# 04-UserIO.net
KiCad netlist of a schematic drawn in Altium Designer
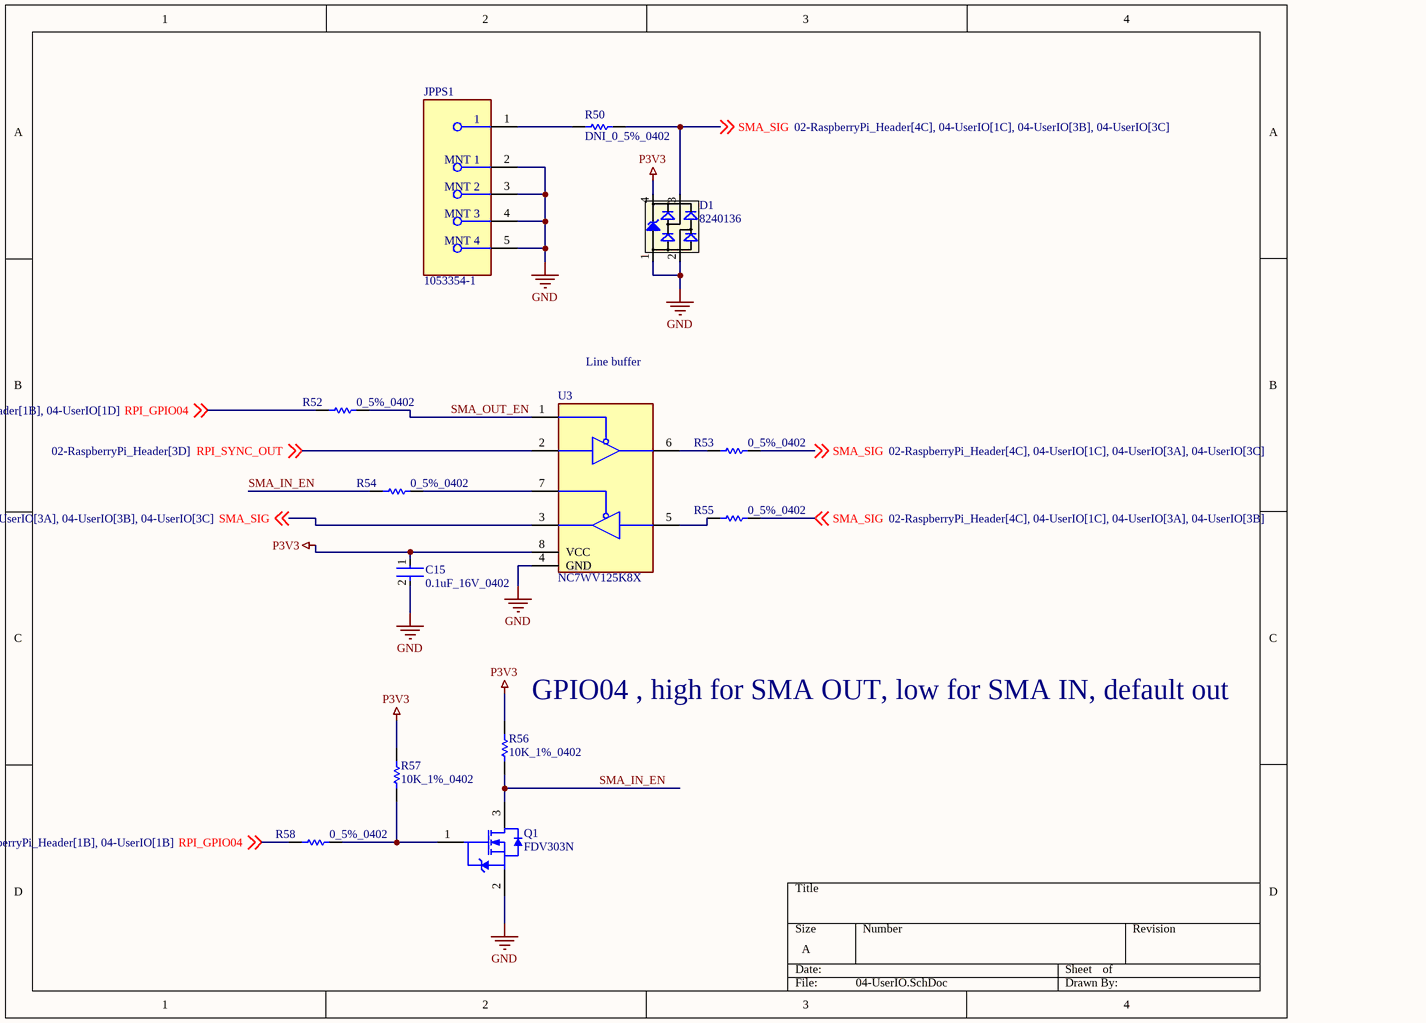
[diagram p0: 04-UserIO.SchDoc]

(export (version "E")
  (design (tool "Eeschema 10.0.6"))
  (components
    (comp (ref "C15")
      (value "0.1uF_16V_0402")
      (footprint "FP-GRM15-MFG")
      (description "CAP CER 0.1UF 16V X7R 0402")
      (fields (field (name "MANUFACTURER PART NUMBER") "GRM155R71C104KA88D") (field (name "TOLERANCE") "10%"))
      (libsource (lib "Altium Content Vault") (part "236180d848d6139a670b325ea6854c9"))
    )
    (comp (ref "D1")
      (value "8240136")
      (footprint "SOT143-4L")
      (description "TVS Diode WE-TVS-HS, VRWM=3.3V")
      (fields (field (name "MANUFACTURER") "Wuerth Elektronik"))
      (libsource (lib "Altium Content Vault") (part "WE-TVS-HS-4"))
    )
    (comp (ref "JPPS1")
      (value "1053354-1")
      (footprint "FP-1053354-1-MFG")
      (description "CONN SMA JACK STR 50 OHM PCB")
      (libsource (lib "Altium Content Vault") (part "c65b8a639cdaef1819ea20b5466f8fa"))
    )
    (comp (ref "Q1")
      (value "FDV303N")
      (footprint "FAIR-FDV303N-3_V")
      (fields (field (name "MANUFACTURER") "Fairchild"))
      (libsource (lib "Altium Content Vault") (part "NEMOS-GSD-3_D"))
    )
    (comp (ref "R50")
      (value "DNI_0_5%_0402")
      (footprint "RESC1005X40X25NL05T10")
      (fields (field (name "MANUFACTURER") "Yageo / Phycomp") (field (name "PART NUMBER") "RC0402JR-070RL"))
      (libsource (lib "Altium Content Vault") (part "RES"))
    )
    (comp (ref "R52")
      (value "0_5%_0402")
      (footprint "RESC1005X40X25NL05T10")
      (fields (field (name "MANUFACTURER") "Yageo / Phycomp") (field (name "PART NUMBER") "RC0402JR-070RL"))
      (libsource (lib "Altium Content Vault") (part "RES"))
    )
    (comp (ref "R53")
      (value "0_5%_0402")
      (footprint "RESC1005X40X25NL05T10")
      (fields (field (name "MANUFACTURER") "Yageo / Phycomp") (field (name "PART NUMBER") "RC0402JR-070RL"))
      (libsource (lib "Altium Content Vault") (part "RES"))
    )
    (comp (ref "R54")
      (value "0_5%_0402")
      (footprint "RESC1005X40X25NL05T10")
      (fields (field (name "MANUFACTURER") "Yageo / Phycomp") (field (name "PART NUMBER") "RC0402JR-070RL"))
      (libsource (lib "Altium Content Vault") (part "RES"))
    )
    (comp (ref "R55")
      (value "0_5%_0402")
      (footprint "RESC1005X40X25NL05T10")
      (fields (field (name "MANUFACTURER") "Yageo / Phycomp") (field (name "PART NUMBER") "RC0402JR-070RL"))
      (libsource (lib "Altium Content Vault") (part "RES"))
    )
    (comp (ref "R56")
      (value "10K_1%_0402")
      (footprint "RESC1005X40X25LL05T05")
      (description "Chip Resistor, 10 KOhm, +/- 1%, 0.1 W, -55 to 155 degC, 0402 (1005 Metric), RoHS, Tape and Reel")
      (fields (field (name "TOLERANCE") "1%") (field (name "MANUFACTURER") "Panasonic"))
      (libsource (lib "Altium Content Vault") (part "RES-2"))
    )
    (comp (ref "R57")
      (value "10K_1%_0402")
      (footprint "RESC1005X40X25LL05T05")
      (description "Chip Resistor, 10 KOhm, +/- 1%, 0.1 W, -55 to 155 degC, 0402 (1005 Metric), RoHS, Tape and Reel")
      (fields (field (name "TOLERANCE") "1%") (field (name "MANUFACTURER") "Panasonic"))
      (libsource (lib "Altium Content Vault") (part "RES-2"))
    )
    (comp (ref "R58")
      (value "0_5%_0402")
      (footprint "RESC1005X40X25NL05T10")
      (fields (field (name "MANUFACTURER") "Yageo / Phycomp") (field (name "PART NUMBER") "RC0402JR-070RL"))
      (libsource (lib "Altium Content Vault") (part "RES"))
    )
    (comp (ref "U3")
      (value "NC7WV125K8X")
      (footprint "SamacSys:SOP50P310X90-8N")
      (description "Integrated Circuit")
      (fields (field (name "MOUSER PART NUMBER") "512-NC7WV125K8X"))
      (libsource (lib "SamacSys") (part "NC7WV125K8X"))
    )
  )
  (nets
    (net (code "1") (name "/SMA_IN_EN") (class "Default")
      (node (ref "Q1") (pin "3") (pinfunction "D_3") (pintype "passive"))
      (node (ref "R54") (pin "1") (pinfunction "1_1") (pintype "passive"))
      (node (ref "R56") (pin "1") (pinfunction "1_1") (pintype "passive"))
    )
    (net (code "2") (name "/SMA_OUT_EN") (class "Default")
      (node (ref "R52") (pin "2") (pinfunction "2_2") (pintype "passive"))
      (node (ref "U3") (pin "1") (pintype "passive"))
    )
    (net (code "3") (name "GND") (class "Default")
      (node (ref "C15") (pin "2") (pinfunction "2_2") (pintype "passive"))
      (node (ref "D1") (pin "1") (pinfunction "GND_1") (pintype "passive"))
      (node (ref "D1") (pin "2") (pinfunction "I/O1_2") (pintype "passive"))
      (node (ref "JPPS1") (pin "2") (pinfunction "MNT_1_2") (pintype "passive"))
      (node (ref "JPPS1") (pin "3") (pinfunction "MNT_2_3") (pintype "passive"))
      (node (ref "JPPS1") (pin "4") (pinfunction "MNT_3_4") (pintype "passive"))
      (node (ref "JPPS1") (pin "5") (pinfunction "MNT_4_5") (pintype "passive"))
      (node (ref "Q1") (pin "2") (pinfunction "S_2") (pintype "passive"))
      (node (ref "U3") (pin "4") (pinfunction "GND_4") (pintype "passive"))
    )
    (net (code "4") (name "Net-(JPPS1-Pad1)") (class "Default")
      (node (ref "JPPS1") (pin "1") (pinfunction "1_1") (pintype "passive"))
      (node (ref "R50") (pin "2") (pinfunction "2_2") (pintype "passive"))
    )
    (net (code "5") (name "Net-(Q1-G)") (class "Default")
      (node (ref "Q1") (pin "1") (pinfunction "G_1") (pintype "passive"))
      (node (ref "R57") (pin "1") (pinfunction "1_1") (pintype "passive"))
      (node (ref "R58") (pin "2") (pinfunction "2_2") (pintype "passive"))
    )
    (net (code "6") (name "Net-(R53-Pad1)") (class "Default")
      (node (ref "R53") (pin "1") (pinfunction "1_1") (pintype "passive"))
      (node (ref "U3") (pin "6") (pintype "passive"))
    )
    (net (code "7") (name "Net-(R54-Pad2)") (class "Default")
      (node (ref "R54") (pin "2") (pinfunction "2_2") (pintype "passive"))
      (node (ref "U3") (pin "7") (pintype "passive"))
    )
    (net (code "8") (name "Net-(R55-Pad1)") (class "Default")
      (node (ref "R55") (pin "1") (pinfunction "1_1") (pintype "passive"))
      (node (ref "U3") (pin "5") (pintype "passive"))
    )
    (net (code "9") (name "P3V3") (class "Default")
      (node (ref "C15") (pin "1") (pinfunction "1_1") (pintype "passive"))
      (node (ref "D1") (pin "4") (pinfunction "VDD_4") (pintype "passive"))
      (node (ref "R56") (pin "2") (pinfunction "2_2") (pintype "passive"))
      (node (ref "R57") (pin "2") (pinfunction "2_2") (pintype "passive"))
      (node (ref "U3") (pin "8") (pinfunction "VCC_8") (pintype "passive"))
    )
    (net (code "10") (name "RPI_GPIO04") (class "Default")
      (node (ref "R52") (pin "1") (pinfunction "1_1") (pintype "passive"))
      (node (ref "R58") (pin "1") (pinfunction "1_1") (pintype "passive"))
    )
    (net (code "11") (name "RPI_SYNC_OUT") (class "Default") (node (ref "U3") (pin "2") (pintype "passive")))
    (net (code "12") (name "SMA_SIG") (class "Default")
      (node (ref "D1") (pin "3") (pinfunction "I/O2_3") (pintype "passive"))
      (node (ref "R50") (pin "1") (pinfunction "1_1") (pintype "passive"))
      (node (ref "R53") (pin "2") (pinfunction "2_2") (pintype "passive"))
      (node (ref "R55") (pin "2") (pinfunction "2_2") (pintype "passive"))
      (node (ref "U3") (pin "3") (pintype "passive"))
    )
  )
)
